# Balancer.net
KiCad netlist of a schematic drawn in EAGLE
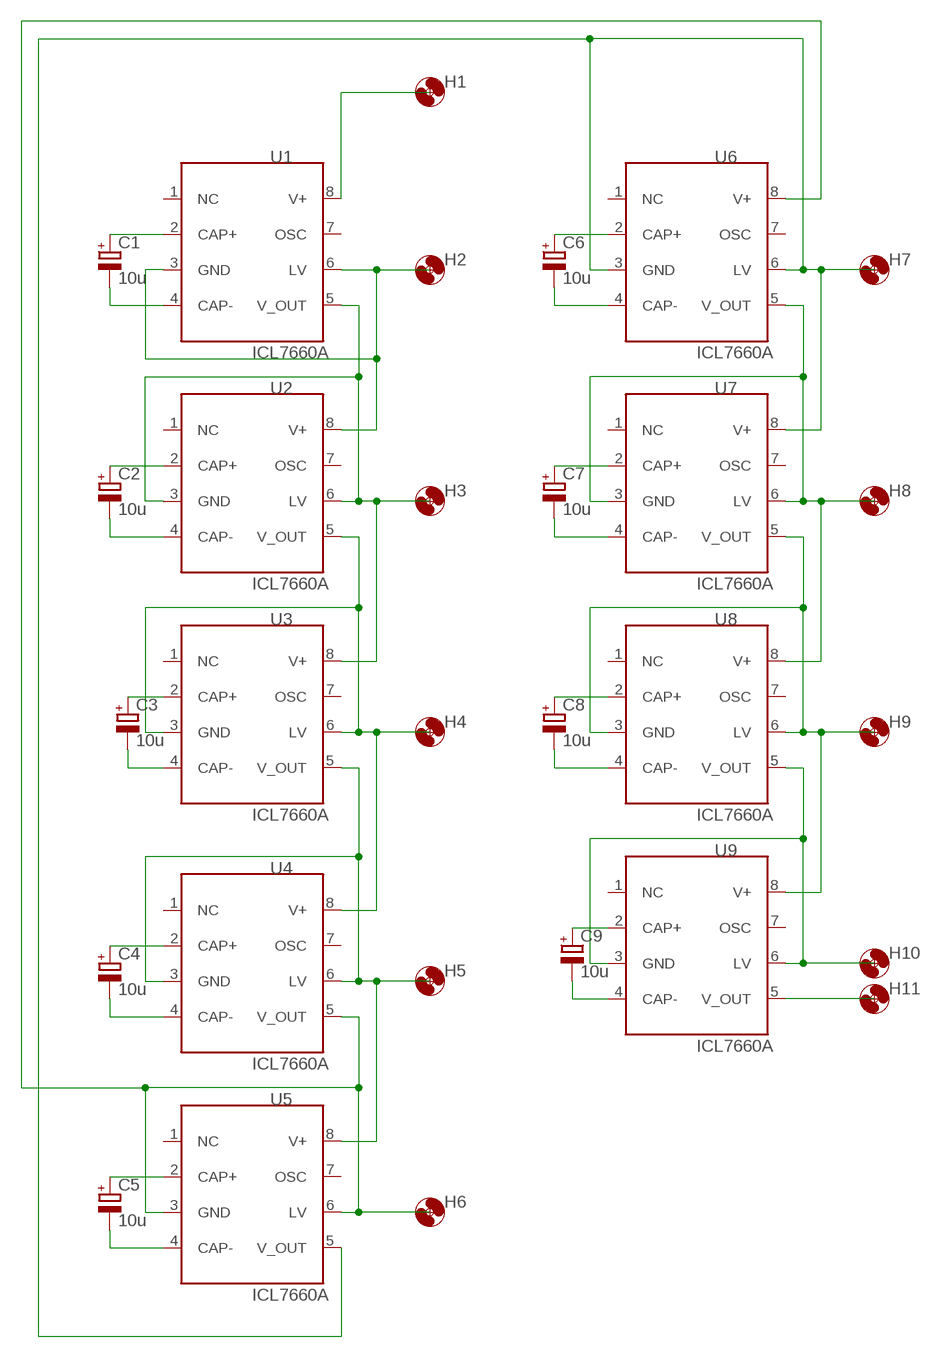
[diagram p0: schematic, sheet 1]

(export (version "E")
  (design (tool "Eeschema 10.0.6"))
  (components
    (comp (ref "C1")
      (value "10u")
      (footprint "eagle-import:CT3216")
      (libsource (lib "eagle-import") (part "CPOL-EUCT3216"))
    )
    (comp (ref "C2")
      (value "10u")
      (footprint "eagle-import:CT3216")
      (libsource (lib "eagle-import") (part "CPOL-EUCT3216"))
    )
    (comp (ref "C3")
      (value "10u")
      (footprint "eagle-import:CT3216")
      (libsource (lib "eagle-import") (part "CPOL-EUCT3216"))
    )
    (comp (ref "C4")
      (value "10u")
      (footprint "eagle-import:CT3216")
      (libsource (lib "eagle-import") (part "CPOL-EUCT3216"))
    )
    (comp (ref "C5")
      (value "10u")
      (footprint "eagle-import:CT3216")
      (libsource (lib "eagle-import") (part "CPOL-EUCT3216"))
    )
    (comp (ref "C6")
      (value "10u")
      (footprint "eagle-import:CT3216")
      (libsource (lib "eagle-import") (part "CPOL-EUCT3216"))
    )
    (comp (ref "C7")
      (value "10u")
      (footprint "eagle-import:CT3216")
      (libsource (lib "eagle-import") (part "CPOL-EUCT3216"))
    )
    (comp (ref "C8")
      (value "10u")
      (footprint "eagle-import:CT3216")
      (libsource (lib "eagle-import") (part "CPOL-EUCT3216"))
    )
    (comp (ref "C9")
      (value "10u")
      (footprint "eagle-import:CT3216")
      (libsource (lib "eagle-import") (part "CPOL-EUCT3216"))
    )
    (comp (ref "H1")
      (value "MOUNT-HOLE3.0")
      (footprint "eagle-import:3,0")
      (libsource (lib "eagle-import") (part "MOUNT-HOLE3.0"))
    )
    (comp (ref "H2")
      (value "MOUNT-HOLE3.0")
      (footprint "eagle-import:3,0")
      (libsource (lib "eagle-import") (part "MOUNT-HOLE3.0"))
    )
    (comp (ref "H3")
      (value "MOUNT-HOLE3.0")
      (footprint "eagle-import:3,0")
      (libsource (lib "eagle-import") (part "MOUNT-HOLE3.0"))
    )
    (comp (ref "H4")
      (value "MOUNT-HOLE3.0")
      (footprint "eagle-import:3,0")
      (libsource (lib "eagle-import") (part "MOUNT-HOLE3.0"))
    )
    (comp (ref "H5")
      (value "MOUNT-HOLE3.0")
      (footprint "eagle-import:3,0")
      (libsource (lib "eagle-import") (part "MOUNT-HOLE3.0"))
    )
    (comp (ref "H6")
      (value "MOUNT-HOLE3.0")
      (footprint "eagle-import:3,0")
      (libsource (lib "eagle-import") (part "MOUNT-HOLE3.0"))
    )
    (comp (ref "H7")
      (value "MOUNT-HOLE3.0")
      (footprint "eagle-import:3,0")
      (libsource (lib "eagle-import") (part "MOUNT-HOLE3.0"))
    )
    (comp (ref "H8")
      (value "MOUNT-HOLE3.0")
      (footprint "eagle-import:3,0")
      (libsource (lib "eagle-import") (part "MOUNT-HOLE3.0"))
    )
    (comp (ref "H9")
      (value "MOUNT-HOLE3.0")
      (footprint "eagle-import:3,0")
      (libsource (lib "eagle-import") (part "MOUNT-HOLE3.0"))
    )
    (comp (ref "H10")
      (value "MOUNT-HOLE3.0")
      (footprint "eagle-import:3,0")
      (libsource (lib "eagle-import") (part "MOUNT-HOLE3.0"))
    )
    (comp (ref "H11")
      (value "MOUNT-HOLE3.0")
      (footprint "eagle-import:3,0")
      (libsource (lib "eagle-import") (part "MOUNT-HOLE3.0"))
    )
    (comp (ref "U1")
      (value "ICL7660A")
      (footprint "eagle-import:SO08")
      (libsource (lib "eagle-import") (part "ICL7660A"))
    )
    (comp (ref "U2")
      (value "ICL7660A")
      (footprint "eagle-import:SO08")
      (libsource (lib "eagle-import") (part "ICL7660A"))
    )
    (comp (ref "U3")
      (value "ICL7660A")
      (footprint "eagle-import:SO08")
      (libsource (lib "eagle-import") (part "ICL7660A"))
    )
    (comp (ref "U4")
      (value "ICL7660A")
      (footprint "eagle-import:SO08")
      (libsource (lib "eagle-import") (part "ICL7660A"))
    )
    (comp (ref "U5")
      (value "ICL7660A")
      (footprint "eagle-import:SO08")
      (libsource (lib "eagle-import") (part "ICL7660A"))
    )
    (comp (ref "U6")
      (value "ICL7660A")
      (footprint "eagle-import:SO08")
      (libsource (lib "eagle-import") (part "ICL7660A"))
    )
    (comp (ref "U7")
      (value "ICL7660A")
      (footprint "eagle-import:SO08")
      (libsource (lib "eagle-import") (part "ICL7660A"))
    )
    (comp (ref "U8")
      (value "ICL7660A")
      (footprint "eagle-import:SO08")
      (libsource (lib "eagle-import") (part "ICL7660A"))
    )
    (comp (ref "U9")
      (value "ICL7660A")
      (footprint "eagle-import:SO08")
      (libsource (lib "eagle-import") (part "ICL7660A"))
    )
  )
  (nets
    (net (code "1") (name "Net-(U1-CAP+)") (class "Default")
      (node (ref "C1") (pin "+") (pinfunction "+_+") (pintype "passive"))
      (node (ref "U1") (pin "2") (pinfunction "CAP+_2") (pintype "bidirectional"))
    )
    (net (code "2") (name "Net-(U1-CAP-)") (class "Default")
      (node (ref "C1") (pin "-") (pinfunction "-_-") (pintype "passive"))
      (node (ref "U1") (pin "4") (pinfunction "CAP-_4") (pintype "bidirectional"))
    )
    (net (code "3") (name "Net-(U1-GND)") (class "Default")
      (node (ref "H2") (pin "P$1") (pinfunction "P$1_P$1") (pintype "bidirectional"))
      (node (ref "U1") (pin "3") (pinfunction "GND_3") (pintype "bidirectional"))
      (node (ref "U1") (pin "6") (pinfunction "LV_6") (pintype "bidirectional"))
      (node (ref "U2") (pin "8") (pinfunction "V+_8") (pintype "bidirectional"))
    )
    (net (code "4") (name "Net-(U1-V+)") (class "Default")
      (node (ref "H1") (pin "P$1") (pinfunction "P$1_P$1") (pintype "bidirectional"))
      (node (ref "U1") (pin "8") (pinfunction "V+_8") (pintype "bidirectional"))
    )
    (net (code "5") (name "Net-(U1-V_OUT)") (class "Default")
      (node (ref "H3") (pin "P$1") (pinfunction "P$1_P$1") (pintype "bidirectional"))
      (node (ref "U1") (pin "5") (pinfunction "V_OUT_5") (pintype "bidirectional"))
      (node (ref "U2") (pin "3") (pinfunction "GND_3") (pintype "bidirectional"))
      (node (ref "U2") (pin "6") (pinfunction "LV_6") (pintype "bidirectional"))
      (node (ref "U3") (pin "8") (pinfunction "V+_8") (pintype "bidirectional"))
    )
    (net (code "6") (name "Net-(U2-CAP+)") (class "Default")
      (node (ref "C2") (pin "+") (pinfunction "+_+") (pintype "passive"))
      (node (ref "U2") (pin "2") (pinfunction "CAP+_2") (pintype "bidirectional"))
    )
    (net (code "7") (name "Net-(U2-CAP-)") (class "Default")
      (node (ref "C2") (pin "-") (pinfunction "-_-") (pintype "passive"))
      (node (ref "U2") (pin "4") (pinfunction "CAP-_4") (pintype "bidirectional"))
    )
    (net (code "8") (name "Net-(U2-V_OUT)") (class "Default")
      (node (ref "H4") (pin "P$1") (pinfunction "P$1_P$1") (pintype "bidirectional"))
      (node (ref "U2") (pin "5") (pinfunction "V_OUT_5") (pintype "bidirectional"))
      (node (ref "U3") (pin "3") (pinfunction "GND_3") (pintype "bidirectional"))
      (node (ref "U3") (pin "6") (pinfunction "LV_6") (pintype "bidirectional"))
      (node (ref "U4") (pin "8") (pinfunction "V+_8") (pintype "bidirectional"))
    )
    (net (code "9") (name "Net-(U3-CAP+)") (class "Default")
      (node (ref "C3") (pin "+") (pinfunction "+_+") (pintype "passive"))
      (node (ref "U3") (pin "2") (pinfunction "CAP+_2") (pintype "bidirectional"))
    )
    (net (code "10") (name "Net-(U3-CAP-)") (class "Default")
      (node (ref "C3") (pin "-") (pinfunction "-_-") (pintype "passive"))
      (node (ref "U3") (pin "4") (pinfunction "CAP-_4") (pintype "bidirectional"))
    )
    (net (code "11") (name "Net-(U3-V_OUT)") (class "Default")
      (node (ref "H5") (pin "P$1") (pinfunction "P$1_P$1") (pintype "bidirectional"))
      (node (ref "U3") (pin "5") (pinfunction "V_OUT_5") (pintype "bidirectional"))
      (node (ref "U4") (pin "3") (pinfunction "GND_3") (pintype "bidirectional"))
      (node (ref "U4") (pin "6") (pinfunction "LV_6") (pintype "bidirectional"))
      (node (ref "U5") (pin "8") (pinfunction "V+_8") (pintype "bidirectional"))
    )
    (net (code "12") (name "Net-(U4-CAP+)") (class "Default")
      (node (ref "C4") (pin "+") (pinfunction "+_+") (pintype "passive"))
      (node (ref "U4") (pin "2") (pinfunction "CAP+_2") (pintype "bidirectional"))
    )
    (net (code "13") (name "Net-(U4-CAP-)") (class "Default")
      (node (ref "C4") (pin "-") (pinfunction "-_-") (pintype "passive"))
      (node (ref "U4") (pin "4") (pinfunction "CAP-_4") (pintype "bidirectional"))
    )
    (net (code "14") (name "Net-(U4-V_OUT)") (class "Default")
      (node (ref "H6") (pin "P$1") (pinfunction "P$1_P$1") (pintype "bidirectional"))
      (node (ref "U4") (pin "5") (pinfunction "V_OUT_5") (pintype "bidirectional"))
      (node (ref "U5") (pin "3") (pinfunction "GND_3") (pintype "bidirectional"))
      (node (ref "U5") (pin "6") (pinfunction "LV_6") (pintype "bidirectional"))
      (node (ref "U6") (pin "8") (pinfunction "V+_8") (pintype "bidirectional"))
    )
    (net (code "15") (name "Net-(U5-CAP+)") (class "Default")
      (node (ref "C5") (pin "+") (pinfunction "+_+") (pintype "passive"))
      (node (ref "U5") (pin "2") (pinfunction "CAP+_2") (pintype "bidirectional"))
    )
    (net (code "16") (name "Net-(U5-CAP-)") (class "Default")
      (node (ref "C5") (pin "-") (pinfunction "-_-") (pintype "passive"))
      (node (ref "U5") (pin "4") (pinfunction "CAP-_4") (pintype "bidirectional"))
    )
    (net (code "17") (name "Net-(U5-V_OUT)") (class "Default")
      (node (ref "H7") (pin "P$1") (pinfunction "P$1_P$1") (pintype "bidirectional"))
      (node (ref "U5") (pin "5") (pinfunction "V_OUT_5") (pintype "bidirectional"))
      (node (ref "U6") (pin "3") (pinfunction "GND_3") (pintype "bidirectional"))
      (node (ref "U6") (pin "6") (pinfunction "LV_6") (pintype "bidirectional"))
      (node (ref "U7") (pin "8") (pinfunction "V+_8") (pintype "bidirectional"))
    )
    (net (code "18") (name "Net-(U6-CAP+)") (class "Default")
      (node (ref "C6") (pin "+") (pinfunction "+_+") (pintype "passive"))
      (node (ref "U6") (pin "2") (pinfunction "CAP+_2") (pintype "bidirectional"))
    )
    (net (code "19") (name "Net-(U6-CAP-)") (class "Default")
      (node (ref "C6") (pin "-") (pinfunction "-_-") (pintype "passive"))
      (node (ref "U6") (pin "4") (pinfunction "CAP-_4") (pintype "bidirectional"))
    )
    (net (code "20") (name "Net-(U6-V_OUT)") (class "Default")
      (node (ref "H8") (pin "P$1") (pinfunction "P$1_P$1") (pintype "bidirectional"))
      (node (ref "U6") (pin "5") (pinfunction "V_OUT_5") (pintype "bidirectional"))
      (node (ref "U7") (pin "3") (pinfunction "GND_3") (pintype "bidirectional"))
      (node (ref "U7") (pin "6") (pinfunction "LV_6") (pintype "bidirectional"))
      (node (ref "U8") (pin "8") (pinfunction "V+_8") (pintype "bidirectional"))
    )
    (net (code "21") (name "Net-(U7-CAP+)") (class "Default")
      (node (ref "C7") (pin "+") (pinfunction "+_+") (pintype "passive"))
      (node (ref "U7") (pin "2") (pinfunction "CAP+_2") (pintype "bidirectional"))
    )
    (net (code "22") (name "Net-(U7-CAP-)") (class "Default")
      (node (ref "C7") (pin "-") (pinfunction "-_-") (pintype "passive"))
      (node (ref "U7") (pin "4") (pinfunction "CAP-_4") (pintype "bidirectional"))
    )
    (net (code "23") (name "Net-(U7-V_OUT)") (class "Default")
      (node (ref "H9") (pin "P$1") (pinfunction "P$1_P$1") (pintype "bidirectional"))
      (node (ref "U7") (pin "5") (pinfunction "V_OUT_5") (pintype "bidirectional"))
      (node (ref "U8") (pin "3") (pinfunction "GND_3") (pintype "bidirectional"))
      (node (ref "U8") (pin "6") (pinfunction "LV_6") (pintype "bidirectional"))
      (node (ref "U9") (pin "8") (pinfunction "V+_8") (pintype "bidirectional"))
    )
    (net (code "24") (name "Net-(U8-CAP+)") (class "Default")
      (node (ref "C8") (pin "+") (pinfunction "+_+") (pintype "passive"))
      (node (ref "U8") (pin "2") (pinfunction "CAP+_2") (pintype "bidirectional"))
    )
    (net (code "25") (name "Net-(U8-CAP-)") (class "Default")
      (node (ref "C8") (pin "-") (pinfunction "-_-") (pintype "passive"))
      (node (ref "U8") (pin "4") (pinfunction "CAP-_4") (pintype "bidirectional"))
    )
    (net (code "26") (name "Net-(U8-V_OUT)") (class "Default")
      (node (ref "H10") (pin "P$1") (pinfunction "P$1_P$1") (pintype "bidirectional"))
      (node (ref "U8") (pin "5") (pinfunction "V_OUT_5") (pintype "bidirectional"))
      (node (ref "U9") (pin "3") (pinfunction "GND_3") (pintype "bidirectional"))
      (node (ref "U9") (pin "6") (pinfunction "LV_6") (pintype "bidirectional"))
    )
    (net (code "27") (name "Net-(U9-CAP+)") (class "Default")
      (node (ref "C9") (pin "+") (pinfunction "+_+") (pintype "passive"))
      (node (ref "U9") (pin "2") (pinfunction "CAP+_2") (pintype "bidirectional"))
    )
    (net (code "28") (name "Net-(U9-CAP-)") (class "Default")
      (node (ref "C9") (pin "-") (pinfunction "-_-") (pintype "passive"))
      (node (ref "U9") (pin "4") (pinfunction "CAP-_4") (pintype "bidirectional"))
    )
    (net (code "29") (name "Net-(U9-V_OUT)") (class "Default")
      (node (ref "H11") (pin "P$1") (pinfunction "P$1_P$1") (pintype "bidirectional"))
      (node (ref "U9") (pin "5") (pinfunction "V_OUT_5") (pintype "bidirectional"))
    )
    (net (code "30") (name "unconnected-(U1-NC-Pad1)") (class "Default")
      (node (ref "U1") (pin "1") (pinfunction "NC_1") (pintype "bidirectional"))
    )
    (net (code "31") (name "unconnected-(U1-OSC-Pad7)") (class "Default")
      (node (ref "U1") (pin "7") (pinfunction "OSC_7") (pintype "bidirectional"))
    )
    (net (code "32") (name "unconnected-(U2-NC-Pad1)") (class "Default")
      (node (ref "U2") (pin "1") (pinfunction "NC_1") (pintype "bidirectional"))
    )
    (net (code "33") (name "unconnected-(U2-OSC-Pad7)") (class "Default")
      (node (ref "U2") (pin "7") (pinfunction "OSC_7") (pintype "bidirectional"))
    )
    (net (code "34") (name "unconnected-(U3-NC-Pad1)") (class "Default")
      (node (ref "U3") (pin "1") (pinfunction "NC_1") (pintype "bidirectional"))
    )
    (net (code "35") (name "unconnected-(U3-OSC-Pad7)") (class "Default")
      (node (ref "U3") (pin "7") (pinfunction "OSC_7") (pintype "bidirectional"))
    )
    (net (code "36") (name "unconnected-(U4-NC-Pad1)") (class "Default")
      (node (ref "U4") (pin "1") (pinfunction "NC_1") (pintype "bidirectional"))
    )
    (net (code "37") (name "unconnected-(U4-OSC-Pad7)") (class "Default")
      (node (ref "U4") (pin "7") (pinfunction "OSC_7") (pintype "bidirectional"))
    )
    (net (code "38") (name "unconnected-(U5-NC-Pad1)") (class "Default")
      (node (ref "U5") (pin "1") (pinfunction "NC_1") (pintype "bidirectional"))
    )
    (net (code "39") (name "unconnected-(U5-OSC-Pad7)") (class "Default")
      (node (ref "U5") (pin "7") (pinfunction "OSC_7") (pintype "bidirectional"))
    )
    (net (code "40") (name "unconnected-(U6-NC-Pad1)") (class "Default")
      (node (ref "U6") (pin "1") (pinfunction "NC_1") (pintype "bidirectional"))
    )
    (net (code "41") (name "unconnected-(U6-OSC-Pad7)") (class "Default")
      (node (ref "U6") (pin "7") (pinfunction "OSC_7") (pintype "bidirectional"))
    )
    (net (code "42") (name "unconnected-(U7-NC-Pad1)") (class "Default")
      (node (ref "U7") (pin "1") (pinfunction "NC_1") (pintype "bidirectional"))
    )
    (net (code "43") (name "unconnected-(U7-OSC-Pad7)") (class "Default")
      (node (ref "U7") (pin "7") (pinfunction "OSC_7") (pintype "bidirectional"))
    )
    (net (code "44") (name "unconnected-(U8-NC-Pad1)") (class "Default")
      (node (ref "U8") (pin "1") (pinfunction "NC_1") (pintype "bidirectional"))
    )
    (net (code "45") (name "unconnected-(U8-OSC-Pad7)") (class "Default")
      (node (ref "U8") (pin "7") (pinfunction "OSC_7") (pintype "bidirectional"))
    )
    (net (code "46") (name "unconnected-(U9-NC-Pad1)") (class "Default")
      (node (ref "U9") (pin "1") (pinfunction "NC_1") (pintype "bidirectional"))
    )
    (net (code "47") (name "unconnected-(U9-OSC-Pad7)") (class "Default")
      (node (ref "U9") (pin "7") (pinfunction "OSC_7") (pintype "bidirectional"))
    )
  )
)
